# MQ9_MQ2_LM35_PT100_IOT.net
KiCad netlist of a schematic drawn in Altium Designer
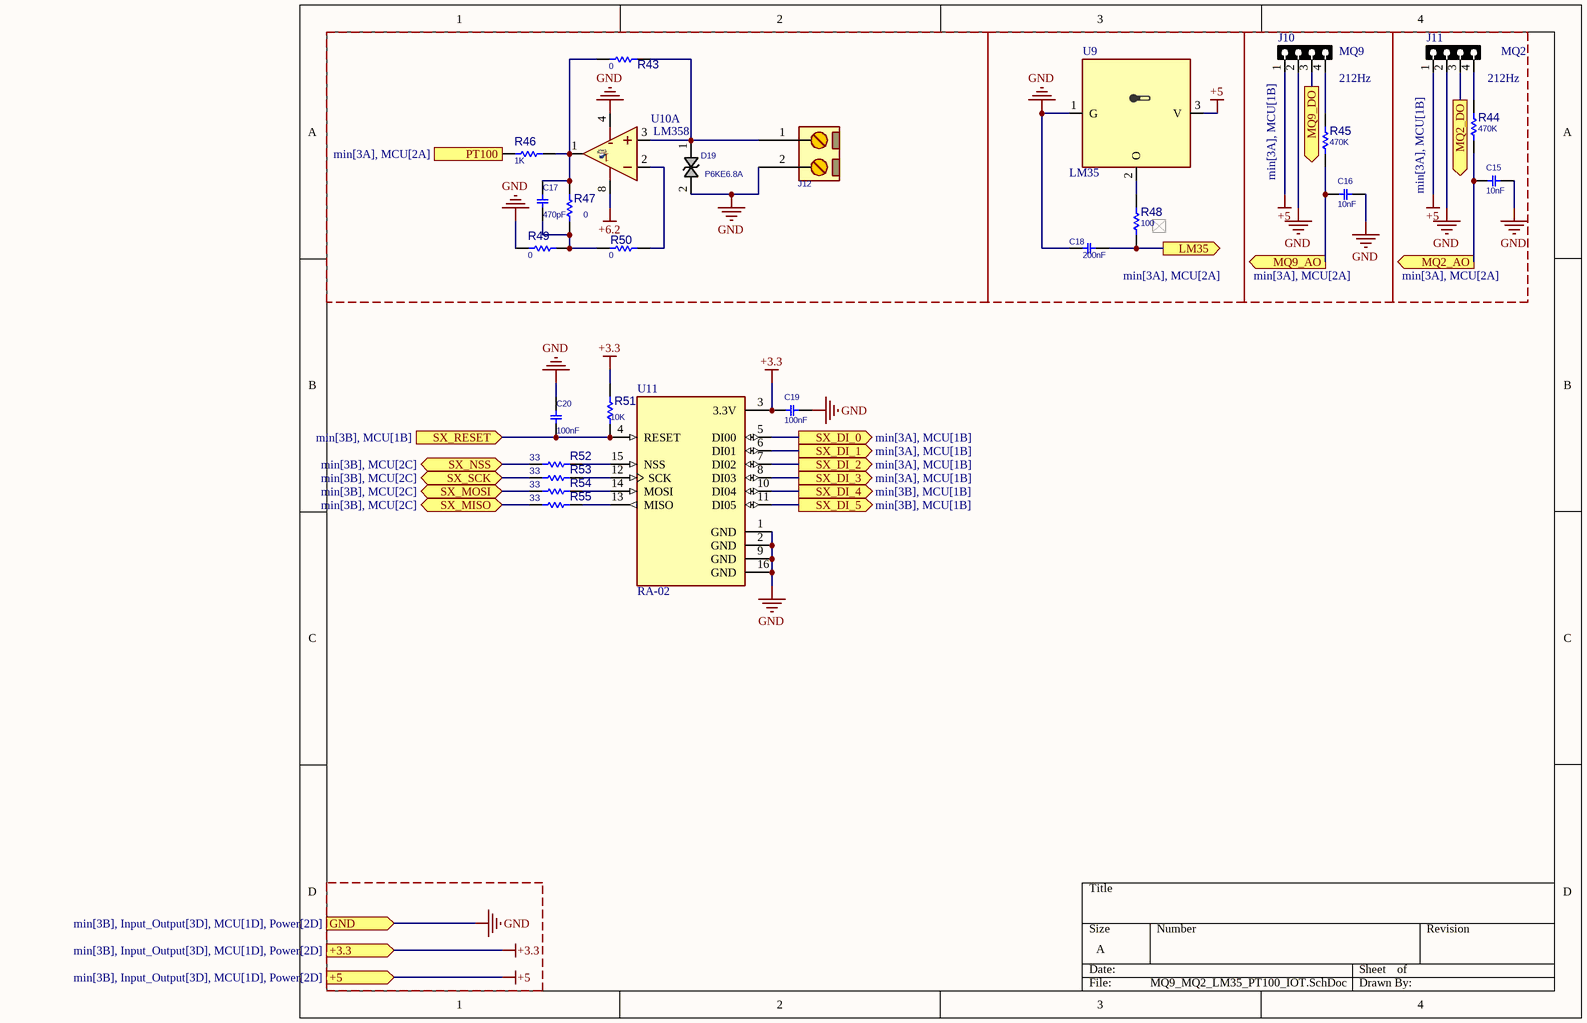
[diagram p0: MQ9_MQ2_LM35_PT100_IOT.SchDoc]

(export (version "E")
  (design (tool "Eeschema 10.0.6"))
  (components
    (comp (ref "C15")
      (value "10nF")
      (footprint "C_CERM_D3")
      (description "CAP, THD, CER MULTI LAYER,")
      (fields (field (name "MANF_P#") "MANF_PART#") (field (name "MANF") "MANF"))
      (libsource (lib "passive_thd") (part "CAP_THD_CER"))
    )
    (comp (ref "C16")
      (value "10nF")
      (footprint "C_CERM_D3")
      (description "CAP, THD, CER MULTI LAYER,")
      (fields (field (name "MANF_P#") "MANF_PART#") (field (name "MANF") "MANF"))
      (libsource (lib "passive_thd") (part "CAP_THD_CER"))
    )
    (comp (ref "C17")
      (value "470pF")
      (footprint "C_CERM_D3")
      (description "CAP, THD, CER MULTI LAYER,")
      (fields (field (name "MANF_P#") "MANF_PART#") (field (name "MANF") "MANF"))
      (libsource (lib "passive_thd") (part "CAP_THD_CER"))
    )
    (comp (ref "C18")
      (value "200nF")
      (footprint "C_CER_D5")
      (description "CAP, THD, CER MULTI LAYER,")
      (fields (field (name "MANF_P#") "MANF_PART#") (field (name "MANF") "MANF"))
      (libsource (lib "passive_thd") (part "CAP_THD_CER"))
    )
    (comp (ref "C19")
      (value "100nF")
      (footprint "C_CERM_D3")
      (description "CAP, THD, CER MULTI LAYER,")
      (fields (field (name "MANF_P#") "MANF_PART#") (field (name "MANF") "MANF"))
      (libsource (lib "passive_thd") (part "CAP_THD_CER"))
    )
    (comp (ref "C20")
      (value "100nF")
      (footprint "C_CERM_D3")
      (description "CAP, THD, CER MULTI LAYER,")
      (fields (field (name "MANF_P#") "MANF_PART#") (field (name "MANF") "MANF"))
      (libsource (lib "passive_thd") (part "CAP_THD_CER"))
    )
    (comp (ref "D19")
      (value "P6KE6.8A")
      (footprint "D_AX05_DO15")
      (description "TVS, ESD PROTECT, Bidirectional")
      (fields (field (name "MANF_P#") "P6KE27CA") (field (name "MANF") "ST, LittleFuse"))
      (libsource (lib "altium-import") (part "root_3_TVS_P6KE27CA_"))
    )
    (comp (ref "J10")
      (value "MQ9")
      (footprint "HDR_F_1X4")
      (description "CONN, HEADER, Female, pitch: 2.54mm, 4POS")
      (libsource (lib "conn_header_2.54mm_st") (part "HDR_F_1X4"))
    )
    (comp (ref "J11")
      (value "MQ2")
      (footprint "HDR_F_1X4")
      (description "CONN, HEADER, Female, pitch: 2.54mm, 4POS")
      (libsource (lib "conn_header_2.54mm_st") (part "HDR_F_1X4"))
    )
    (comp (ref "J12")
      (value "CONN_GMSTB2")
      (footprint "GMSTB762_2")
      (description "CONN, PHOENIX GMSTB, 7.62mm pitch")
      (fields (field (name "MANF_P#") "GMSTB 2,5/2-G-7,62"))
      (libsource (lib "conn_terminalB") (part "CONN_GMSTB762_2"))
    )
    (comp (ref "R43")
      (value "0")
      (footprint "R0125W_AX03")
      (description "RESISTOR, THD")
      (fields (field (name "MANF_P#") "RK73H1ETTP4701F") (field (name "MANF") "KOA SPEER"))
      (libsource (lib "passive_thd") (part "RES_THD"))
    )
    (comp (ref "R44")
      (value "470K")
      (footprint "R025W_AX_VER")
      (description "RESISTOR, THD")
      (fields (field (name "MANF_P#") "RK73H1ETTP4701F") (field (name "MANF") "KOA SPEER"))
      (libsource (lib "passive_thd") (part "RES_THD"))
    )
    (comp (ref "R45")
      (value "470K")
      (footprint "R025W_AX_VER")
      (description "RESISTOR, THD")
      (fields (field (name "MANF_P#") "RK73H1ETTP4701F") (field (name "MANF") "KOA SPEER"))
      (libsource (lib "passive_thd") (part "RES_THD"))
    )
    (comp (ref "R46")
      (value "1K")
      (footprint "R0125W_AX03")
      (description "RESISTOR, THD")
      (fields (field (name "MANF_P#") "RK73H1ETTP4701F") (field (name "MANF") "KOA SPEER"))
      (libsource (lib "passive_thd") (part "RES_THD"))
    )
    (comp (ref "R47")
      (value "0")
      (footprint "R0125W_AX03")
      (description "RESISTOR, THD")
      (fields (field (name "MANF_P#") "RK73H1ETTP4701F") (field (name "MANF") "KOA SPEER"))
      (libsource (lib "passive_thd") (part "RES_THD"))
    )
    (comp (ref "R48")
      (value "100")
      (footprint "R025W_AX04")
      (description "RESISTOR, THD")
      (fields (field (name "MANF_P#") "RK73H1ETTP4701F") (field (name "MANF") "KOA SPEER"))
      (libsource (lib "passive_thd") (part "RES_THD"))
    )
    (comp (ref "R49")
      (value "0")
      (footprint "R0125W_AX03")
      (description "RESISTOR, THD")
      (fields (field (name "MANF_P#") "RK73H1ETTP4701F") (field (name "MANF") "KOA SPEER"))
      (libsource (lib "passive_thd") (part "RES_THD"))
    )
    (comp (ref "R50")
      (value "0")
      (footprint "R0125W_AX03")
      (description "RESISTOR, THD")
      (fields (field (name "MANF_P#") "RK73H1ETTP4701F") (field (name "MANF") "KOA SPEER"))
      (libsource (lib "passive_thd") (part "RES_THD"))
    )
    (comp (ref "R51")
      (value "10K")
      (footprint "R0125W_AX03")
      (description "RESISTOR, THD")
      (fields (field (name "MANF_P#") "RK73H1ETTP4701F") (field (name "MANF") "KOA SPEER"))
      (libsource (lib "passive_thd") (part "RES_THD"))
    )
    (comp (ref "R52")
      (value "33")
      (footprint "R1206")
      (description "RESISTOR, SMD")
      (libsource (lib "passive_smd") (part "RES_SMD"))
    )
    (comp (ref "R53")
      (value "33")
      (footprint "R1206")
      (description "RESISTOR, SMD")
      (libsource (lib "passive_smd") (part "RES_SMD"))
    )
    (comp (ref "R54")
      (value "33")
      (footprint "R1206")
      (description "RESISTOR, SMD")
      (libsource (lib "passive_smd") (part "RES_SMD"))
    )
    (comp (ref "R55")
      (value "33")
      (footprint "R1206")
      (description "RESISTOR, SMD")
      (libsource (lib "passive_smd") (part "RES_SMD"))
    )
    (comp (ref "U9")
      (value "LM35")
      (footprint "TO92_3")
      (description "SENSOR, TEMP, ANALOG, -55~150oC, 4~20Vcc, Out 0mV + 10mV/oC")
      (fields (field (name "MANF_P#") "LM35CZ, LM35CAZ or LM35DZ") (field (name "MANF") "TI"))
      (libsource (lib "sensor_temp&humidity") (part "TMP_LM35_TO92"))
    )
    (comp (ref "U10")
      (value "LM358")
      (footprint "DIP_8")
      (description "AMP, Dual, Low-Power")
      (fields (field (name "MANF") "Texas Instruments, Fairchild") (field (name "MANF_P#") "LM358AN"))
      (libsource (lib "amp") (part "LM358_DIP8"))
    )
    (comp (ref "U11")
      (value "RA-02")
      (footprint "RA-02")
      (fields (field (name "MF") "Ai-Thinker"))
      (libsource (lib "RA-02") (part "RA-02"))
    )
  )
  (nets
    (net (code "1") (name "+3.3") (class "Default")
      (node (ref "C19") (pin "2") (pinfunction "2_2") (pintype "passive"))
      (node (ref "R51") (pin "1") (pinfunction "1_1") (pintype "passive"))
      (node (ref "U11") (pin "3") (pinfunction "3.3V_3") (pintype "power_in"))
    )
    (net (code "2") (name "+5") (class "Default")
      (node (ref "J10") (pin "1") (pinfunction "1_1") (pintype "passive"))
      (node (ref "J11") (pin "1") (pinfunction "1_1") (pintype "passive"))
      (node (ref "U9") (pin "3") (pinfunction "V_3") (pintype "passive"))
    )
    (net (code "3") (name "+6.2") (class "Default")
      (node (ref "U10") (pin "8") (pinfunction "V+_8") (pintype "passive"))
    )
    (net (code "4") (name "/LM35") (class "Default")
      (node (ref "C18") (pin "2") (pinfunction "2_2") (pintype "passive"))
      (node (ref "R48") (pin "2") (pinfunction "2_2") (pintype "passive"))
    )
    (net (code "5") (name "/MQ2_AO") (class "Default")
      (node (ref "C15") (pin "2") (pinfunction "2_2") (pintype "passive"))
      (node (ref "R44") (pin "1") (pinfunction "1_1") (pintype "passive"))
    )
    (net (code "6") (name "/MQ2_DO") (class "Default")
      (node (ref "J11") (pin "3") (pinfunction "3_3") (pintype "passive"))
    )
    (net (code "7") (name "/MQ9_AO") (class "Default")
      (node (ref "C16") (pin "2") (pinfunction "2_2") (pintype "passive"))
      (node (ref "R45") (pin "1") (pinfunction "1_1") (pintype "passive"))
    )
    (net (code "8") (name "/MQ9_DO") (class "Default")
      (node (ref "J10") (pin "3") (pinfunction "3_3") (pintype "passive"))
    )
    (net (code "9") (name "/PT100") (class "Default")
      (node (ref "R46") (pin "2") (pinfunction "2_2") (pintype "passive"))
    )
    (net (code "10") (name "/SX_DI_0") (class "Default")
      (node (ref "U11") (pin "5") (pinfunction "DI00_5") (pintype "bidirectional"))
    )
    (net (code "11") (name "/SX_DI_1") (class "Default")
      (node (ref "U11") (pin "6") (pinfunction "DI01_6") (pintype "bidirectional"))
    )
    (net (code "12") (name "/SX_DI_2") (class "Default")
      (node (ref "U11") (pin "7") (pinfunction "DI02_7") (pintype "bidirectional"))
    )
    (net (code "13") (name "/SX_DI_3") (class "Default")
      (node (ref "U11") (pin "8") (pinfunction "DI03_8") (pintype "bidirectional"))
    )
    (net (code "14") (name "/SX_DI_4") (class "Default")
      (node (ref "U11") (pin "10") (pinfunction "DI04_10") (pintype "bidirectional"))
    )
    (net (code "15") (name "/SX_DI_5") (class "Default")
      (node (ref "U11") (pin "11") (pinfunction "DI05_11") (pintype "bidirectional"))
    )
    (net (code "16") (name "/SX_MISO") (class "Default")
      (node (ref "R55") (pin "1") (pinfunction "1_1") (pintype "passive"))
    )
    (net (code "17") (name "/SX_MOSI") (class "Default")
      (node (ref "R54") (pin "1") (pinfunction "1_1") (pintype "passive"))
    )
    (net (code "18") (name "/SX_NSS") (class "Default")
      (node (ref "R52") (pin "1") (pinfunction "1_1") (pintype "passive"))
    )
    (net (code "19") (name "/SX_RESET") (class "Default")
      (node (ref "C20") (pin "1") (pinfunction "1_1") (pintype "passive"))
      (node (ref "R51") (pin "2") (pinfunction "2_2") (pintype "passive"))
      (node (ref "U11") (pin "4") (pinfunction "RESET_4") (pintype "input"))
    )
    (net (code "20") (name "/SX_SCK") (class "Default")
      (node (ref "R53") (pin "1") (pinfunction "1_1") (pintype "passive"))
    )
    (net (code "21") (name "GND") (class "Default")
      (node (ref "C15") (pin "1") (pinfunction "1_1") (pintype "passive"))
      (node (ref "C16") (pin "1") (pinfunction "1_1") (pintype "passive"))
      (node (ref "C18") (pin "1") (pinfunction "1_1") (pintype "passive"))
      (node (ref "C19") (pin "1") (pinfunction "1_1") (pintype "passive"))
      (node (ref "C20") (pin "2") (pinfunction "2_2") (pintype "passive"))
      (node (ref "D19") (pin "2") (pinfunction "2_2") (pintype "passive"))
      (node (ref "J10") (pin "2") (pinfunction "2_2") (pintype "passive"))
      (node (ref "J11") (pin "2") (pinfunction "2_2") (pintype "passive"))
      (node (ref "J12") (pin "2") (pinfunction "2_2") (pintype "passive"))
      (node (ref "R49") (pin "2") (pinfunction "2_2") (pintype "passive"))
      (node (ref "U10") (pin "4") (pinfunction "V-_4") (pintype "passive"))
      (node (ref "U11") (pin "1") (pinfunction "GND_1") (pintype "power_in"))
      (node (ref "U11") (pin "16") (pinfunction "GND_16") (pintype "power_in"))
      (node (ref "U11") (pin "2") (pinfunction "GND_2") (pintype "power_in"))
      (node (ref "U11") (pin "9") (pinfunction "GND_9") (pintype "power_in"))
      (node (ref "U9") (pin "1") (pinfunction "G_1") (pintype "passive"))
    )
    (net (code "22") (name "Net-(C17-Pad1)") (class "Default")
      (node (ref "C17") (pin "1") (pinfunction "1_1") (pintype "passive"))
      (node (ref "R47") (pin "2") (pinfunction "2_2") (pintype "passive"))
      (node (ref "R49") (pin "1") (pinfunction "1_1") (pintype "passive"))
      (node (ref "R50") (pin "1") (pinfunction "1_1") (pintype "passive"))
    )
    (net (code "23") (name "Net-(J10-Pad4)") (class "Default")
      (node (ref "J10") (pin "4") (pinfunction "4_4") (pintype "passive"))
      (node (ref "R45") (pin "2") (pinfunction "2_2") (pintype "passive"))
    )
    (net (code "24") (name "Net-(J11-Pad4)") (class "Default")
      (node (ref "J11") (pin "4") (pinfunction "4_4") (pintype "passive"))
      (node (ref "R44") (pin "2") (pinfunction "2_2") (pintype "passive"))
    )
    (net (code "25") (name "Net-(U9-O)") (class "Default")
      (node (ref "R48") (pin "1") (pinfunction "1_1") (pintype "passive"))
      (node (ref "U9") (pin "2") (pinfunction "O_2") (pintype "passive"))
    )
    (net (code "26") (name "Net-(U10A-IN+)") (class "Default")
      (node (ref "D19") (pin "1") (pinfunction "1_1") (pintype "passive"))
      (node (ref "J12") (pin "1") (pinfunction "1_1") (pintype "passive"))
      (node (ref "R43") (pin "1") (pinfunction "1_1") (pintype "passive"))
      (node (ref "U10") (pin "3") (pinfunction "IN+_3") (pintype "passive"))
    )
    (net (code "27") (name "Net-(U10A-IN-)") (class "Default")
      (node (ref "R50") (pin "2") (pinfunction "2_2") (pintype "passive"))
      (node (ref "U10") (pin "2") (pinfunction "IN-_2") (pintype "passive"))
    )
    (net (code "28") (name "Net-(U10A-OUT)") (class "Default")
      (node (ref "C17") (pin "2") (pinfunction "2_2") (pintype "passive"))
      (node (ref "R43") (pin "2") (pinfunction "2_2") (pintype "passive"))
      (node (ref "R46") (pin "1") (pinfunction "1_1") (pintype "passive"))
      (node (ref "R47") (pin "1") (pinfunction "1_1") (pintype "passive"))
      (node (ref "U10") (pin "1") (pinfunction "OUT_1") (pintype "passive"))
    )
    (net (code "29") (name "Net-(U11-MISO)") (class "Default")
      (node (ref "R55") (pin "2") (pinfunction "2_2") (pintype "passive"))
      (node (ref "U11") (pin "13") (pinfunction "MISO_13") (pintype "output"))
    )
    (net (code "30") (name "Net-(U11-MOSI)") (class "Default")
      (node (ref "R54") (pin "2") (pinfunction "2_2") (pintype "passive"))
      (node (ref "U11") (pin "14") (pinfunction "MOSI_14") (pintype "input"))
    )
    (net (code "31") (name "Net-(U11-NSS)") (class "Default")
      (node (ref "R52") (pin "2") (pinfunction "2_2") (pintype "passive"))
      (node (ref "U11") (pin "15") (pinfunction "NSS_15") (pintype "input"))
    )
    (net (code "32") (name "Net-(U11-SCK)") (class "Default")
      (node (ref "R53") (pin "2") (pinfunction "2_2") (pintype "passive"))
      (node (ref "U11") (pin "12") (pinfunction "SCK_12") (pintype "input"))
    )
  )
)
